# untitled.net
KiCad netlist of a schematic drawn in EAGLE
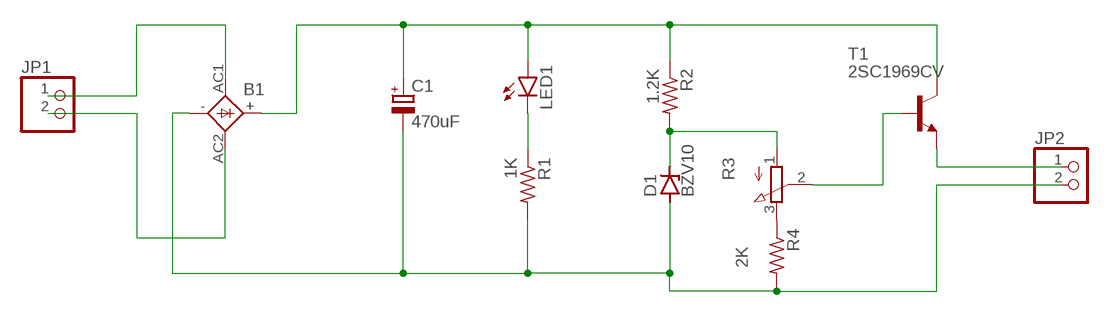
[diagram p0: schematic, sheet 1]

(export (version "E")
  (design (tool "Eeschema 10.0.6"))
  (components
    (comp (ref "B1")
      (value "1KAB")
      (footprint "eagle-import:1KAB")
      (libsource (lib "eagle-import") (part "1KAB"))
    )
    (comp (ref "C1")
      (value "470uF")
      (footprint "eagle-import:E3,5-10")
      (libsource (lib "eagle-import") (part "CPOL-EUE3.5-10"))
    )
    (comp (ref "D1")
      (value "BZV10")
      (footprint "eagle-import:DO34Z7")
      (libsource (lib "eagle-import") (part "BZV10"))
    )
    (comp (ref "JP1")
      (value "PINHD-1X2")
      (footprint "eagle-import:1X02")
      (libsource (lib "eagle-import") (part "PINHD-1X2"))
    )
    (comp (ref "JP2")
      (value "PINHD-1X2")
      (footprint "eagle-import:1X02")
      (libsource (lib "eagle-import") (part "PINHD-1X2"))
    )
    (comp (ref "LED1")
      (value "LED5MM")
      (footprint "eagle-import:LED5MM")
      (libsource (lib "eagle-import") (part "LED5MM"))
    )
    (comp (ref "R1")
      (value "1K")
      (footprint "eagle-import:0309_12")
      (libsource (lib "eagle-import") (part "R-US_0309/12"))
    )
    (comp (ref "R2")
      (value "1.2K")
      (footprint "eagle-import:0309_12")
      (libsource (lib "eagle-import") (part "R-US_0309/12"))
    )
    (comp (ref "R3")
      (value "3RP/1610N")
      (footprint "eagle-import:3RP_1610N")
      (libsource (lib "eagle-import") (part "3RP/1610N"))
    )
    (comp (ref "R4")
      (value "2K")
      (footprint "eagle-import:0309_12")
      (libsource (lib "eagle-import") (part "R-US_0309/12"))
    )
    (comp (ref "T1")
      (value "2SC1969CV")
      (footprint "eagle-import:T-30_V")
      (libsource (lib "eagle-import") (part "2SC1969VC"))
    )
  )
  (nets
    (net (code "1") (name "Net-(B1-Pad-)") (class "Default")
      (node (ref "B1") (pin "-") (pinfunction "-_-") (pintype "passive"))
      (node (ref "C1") (pin "-") (pinfunction "-_-") (pintype "passive"))
      (node (ref "D1") (pin "A") (pinfunction "A_A") (pintype "passive"))
      (node (ref "JP2") (pin "2") (pinfunction "2_2") (pintype "passive"))
      (node (ref "R1") (pin "2") (pinfunction "2_2") (pintype "passive"))
      (node (ref "R4") (pin "2") (pinfunction "2_2") (pintype "passive"))
    )
    (net (code "2") (name "Net-(B1-PadAC1)") (class "Default")
      (node (ref "B1") (pin "AC1") (pinfunction "AC1_AC1") (pintype "passive"))
      (node (ref "JP1") (pin "1") (pinfunction "1_1") (pintype "passive"))
    )
    (net (code "3") (name "Net-(B1-PadAC2)") (class "Default")
      (node (ref "B1") (pin "AC2") (pinfunction "AC2_AC2") (pintype "passive"))
      (node (ref "JP1") (pin "2") (pinfunction "2_2") (pintype "passive"))
    )
    (net (code "4") (name "Net-(LED1-C)") (class "Default")
      (node (ref "LED1") (pin "K") (pinfunction "C_K") (pintype "passive"))
      (node (ref "R1") (pin "1") (pinfunction "1_1") (pintype "passive"))
    )
    (net (code "5") (name "Net-(R3-A)") (class "Default")
      (node (ref "D1") (pin "C") (pinfunction "C_C") (pintype "passive"))
      (node (ref "R2") (pin "2") (pinfunction "2_2") (pintype "passive"))
      (node (ref "R3") (pin "1") (pinfunction "A_1") (pintype "passive"))
    )
    (net (code "6") (name "Net-(R3-E)") (class "Default")
      (node (ref "R3") (pin "3") (pinfunction "E_3") (pintype "passive"))
      (node (ref "R4") (pin "1") (pinfunction "1_1") (pintype "passive"))
    )
    (net (code "7") (name "Net-(R3-S)") (class "Default")
      (node (ref "R3") (pin "2") (pinfunction "S_2") (pintype "passive"))
      (node (ref "T1") (pin "1") (pinfunction "B_1") (pintype "passive"))
    )
    (net (code "8") (name "Net-(T1-C)") (class "Default")
      (node (ref "B1") (pin "+") (pinfunction "+_+") (pintype "passive"))
      (node (ref "C1") (pin "+") (pinfunction "+_+") (pintype "passive"))
      (node (ref "LED1") (pin "A") (pinfunction "A_A") (pintype "passive"))
      (node (ref "R2") (pin "1") (pinfunction "1_1") (pintype "passive"))
      (node (ref "T1") (pin "2") (pinfunction "C_2") (pintype "passive"))
    )
    (net (code "9") (name "Net-(T1-E)") (class "Default")
      (node (ref "JP2") (pin "1") (pinfunction "1_1") (pintype "passive"))
      (node (ref "T1") (pin "3") (pinfunction "E_3") (pintype "passive"))
    )
  )
)
